# ProPrj_universal-fpga-expansion-board_20.net
KiCad netlist of a schematic drawn in EasyEDA Pro
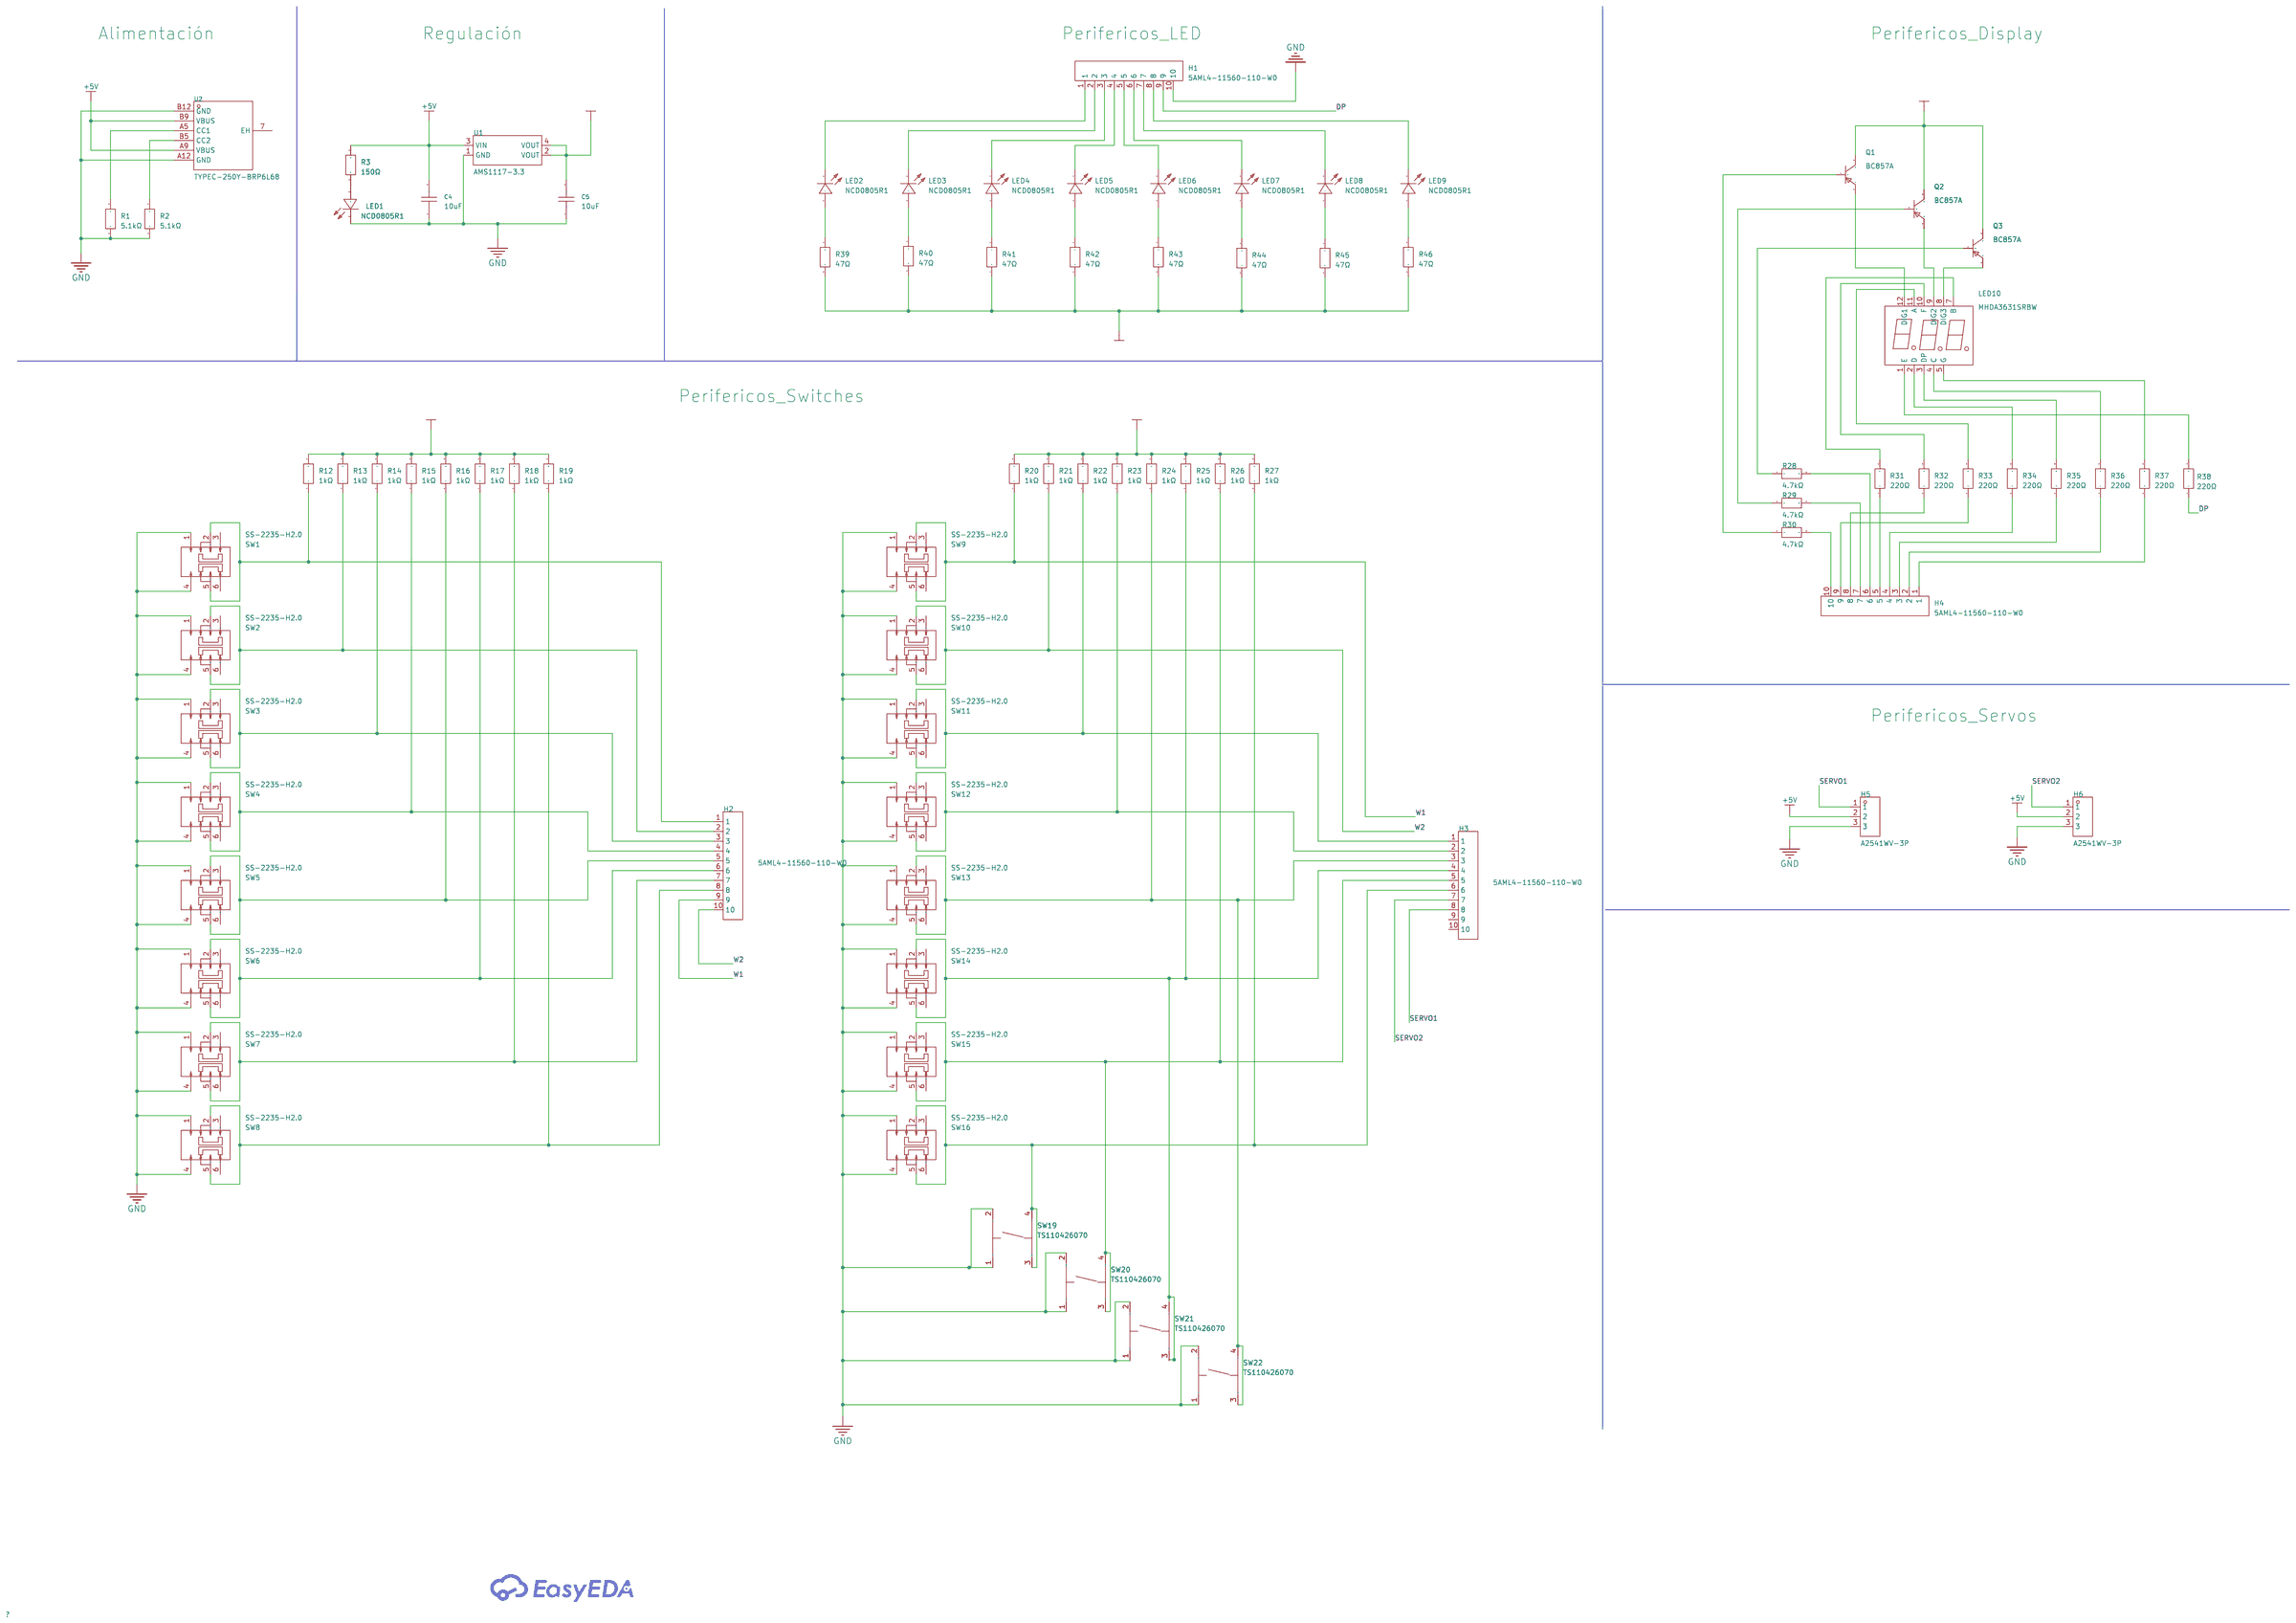
[diagram p0: schematic sheet]

(export (version "E")
  (design (tool "Eeschema 10.0.6"))
  (components
    (comp (ref "C4")
      (value "10uF")
      (footprint "easyedapro:C0603")
      (fields
        (field (name "Manufacturer Part") "CL10A106MQ8NNNC")
        (field (name "Manufacturer") "SAMSUNG(三星)")
      )
      (libsource (lib "easyedapro") (part "CL10A106MQ8NNNC"))
    )
    (comp (ref "C5")
      (value "10uF")
      (footprint "easyedapro:C0603")
      (fields
        (field (name "Manufacturer Part") "CL10A106MQ8NNNC")
        (field (name "Manufacturer") "SAMSUNG(三星)")
      )
      (libsource (lib "easyedapro") (part "CL10A106MQ8NNNC"))
    )
    (comp (ref "H1")
      (value "5AML4-11560-110-W0")
      (footprint "easyedapro:HDR-TH_10P-P2.54-V-M-1")
      (fields (field (name "Manufacturer") "SAMZO(三佐)"))
      (libsource (lib "easyedapro") (part "5AML4-11560-110-W0"))
    )
    (comp (ref "H2")
      (value "5AML4-11560-110-W0")
      (footprint "easyedapro:HDR-TH_10P-P2.54-V-M-1")
      (fields (field (name "Manufacturer") "SAMZO(三佐)"))
      (libsource (lib "easyedapro") (part "5AML4-11560-110-W0"))
    )
    (comp (ref "H3")
      (value "5AML4-11560-110-W0")
      (footprint "easyedapro:HDR-TH_10P-P2.54-V-M-1")
      (fields (field (name "Manufacturer") "SAMZO(三佐)"))
      (libsource (lib "easyedapro") (part "5AML4-11560-110-W0"))
    )
    (comp (ref "H4")
      (value "5AML4-11560-110-W0")
      (footprint "easyedapro:HDR-TH_10P-P2.54-V-M-1")
      (fields (field (name "Manufacturer") "SAMZO(三佐)"))
      (libsource (lib "easyedapro") (part "5AML4-11560-110-W0"))
    )
    (comp (ref "H5")
      (value "A2541WV-3P")
      (footprint "easyedapro:HDR-TH_3P-P2.54-V-M")
      (fields (field (name "Manufacturer") "CJT(长江连接器)"))
      (libsource (lib "easyedapro") (part "A2541WV-3P_C5445396"))
    )
    (comp (ref "H6")
      (value "A2541WV-3P")
      (footprint "easyedapro:HDR-TH_3P-P2.54-V-M")
      (fields (field (name "Manufacturer") "CJT(长江连接器)"))
      (libsource (lib "easyedapro") (part "A2541WV-3P_C5445396"))
    )
    (comp (ref "LED1")
      (value "NCD0805R1")
      (footprint "easyedapro:LED0805-R-RD")
      (fields (field (name "Manufacturer") "国星光电"))
      (libsource (lib "easyedapro") (part "FC-2012HRK-620D"))
    )
    (comp (ref "LED2")
      (value "NCD0805R1")
      (footprint "easyedapro:LED0805-R-RD")
      (fields (field (name "Manufacturer") "国星光电"))
      (libsource (lib "easyedapro") (part "FC-2012HRK-620D"))
    )
    (comp (ref "LED3")
      (value "NCD0805R1")
      (footprint "easyedapro:LED0805-R-RD")
      (fields (field (name "Manufacturer") "国星光电"))
      (libsource (lib "easyedapro") (part "FC-2012HRK-620D"))
    )
    (comp (ref "LED4")
      (value "NCD0805R1")
      (footprint "easyedapro:LED0805-R-RD")
      (fields (field (name "Manufacturer") "国星光电"))
      (libsource (lib "easyedapro") (part "FC-2012HRK-620D"))
    )
    (comp (ref "LED5")
      (value "NCD0805R1")
      (footprint "easyedapro:LED0805-R-RD")
      (fields (field (name "Manufacturer") "国星光电"))
      (libsource (lib "easyedapro") (part "FC-2012HRK-620D"))
    )
    (comp (ref "LED6")
      (value "NCD0805R1")
      (footprint "easyedapro:LED0805-R-RD")
      (fields (field (name "Manufacturer") "国星光电"))
      (libsource (lib "easyedapro") (part "FC-2012HRK-620D"))
    )
    (comp (ref "LED7")
      (value "NCD0805R1")
      (footprint "easyedapro:LED0805-R-RD")
      (fields (field (name "Manufacturer") "国星光电"))
      (libsource (lib "easyedapro") (part "FC-2012HRK-620D"))
    )
    (comp (ref "LED8")
      (value "NCD0805R1")
      (footprint "easyedapro:LED0805-R-RD")
      (fields (field (name "Manufacturer") "国星光电"))
      (libsource (lib "easyedapro") (part "FC-2012HRK-620D"))
    )
    (comp (ref "LED9")
      (value "NCD0805R1")
      (footprint "easyedapro:LED0805-R-RD")
      (fields (field (name "Manufacturer") "国星光电"))
      (libsource (lib "easyedapro") (part "FC-2012HRK-620D"))
    )
    (comp (ref "LED10")
      (value "MHDA3631SRBW")
      (footprint "easyedapro:LED-SEG-TH_11P-L22.5-W14.0-P2.54-S10.18-BL")
      (fields (field (name "Manufacturer") "MEIHUA(美华)"))
      (libsource (lib "easyedapro") (part "MHDA3631SRBW"))
    )
    (comp (ref "Q1")
      (value "BC857A")
      (footprint "easyedapro:SOT-23-3_L3.0-W1.7-P0.95-LS2.9-BR")
      (fields (field (name "Manufacturer") "YFW(佑风微)"))
      (libsource (lib "easyedapro") (part "BC857A_C19626403"))
    )
    (comp (ref "Q2")
      (value "BC857A")
      (footprint "easyedapro:SOT-23-3_L3.0-W1.7-P0.95-LS2.9-BR")
      (fields (field (name "Manufacturer") "YFW(佑风微)"))
      (libsource (lib "easyedapro") (part "BC857A_C19626403"))
    )
    (comp (ref "Q3")
      (value "BC857A")
      (footprint "easyedapro:SOT-23-3_L3.0-W1.7-P0.95-LS2.9-BR")
      (fields (field (name "Manufacturer") "YFW(佑风微)"))
      (libsource (lib "easyedapro") (part "BC857A_C19626403"))
    )
    (comp (ref "R1")
      (value "5.1kΩ")
      (footprint "easyedapro:R1206")
      (fields (field (name "Manufacturer Part") "FRC1206J512 TS") (field (name "Manufacturer") "FOJAN(富捷)"))
      (libsource (lib "easyedapro") (part "FRC1206J512 TS"))
    )
    (comp (ref "R2")
      (value "5.1kΩ")
      (footprint "easyedapro:R1206")
      (fields (field (name "Manufacturer Part") "FRC1206J512 TS") (field (name "Manufacturer") "FOJAN(富捷)"))
      (libsource (lib "easyedapro") (part "FRC1206J512 TS"))
    )
    (comp (ref "R3")
      (value "150Ω")
      (footprint "easyedapro:R1206")
      (fields
        (field (name "Manufacturer Part") "SC1206J1500F8ANRH")
        (field (name "Manufacturer") "Sunway(信维通信)")
      )
      (libsource (lib "easyedapro") (part "SC1206J1500F8ANRH"))
    )
    (comp (ref "R12")
      (value "1kΩ")
      (footprint "easyedapro:R1206")
      (fields (field (name "Manufacturer Part") "AF1206FR-071KL") (field (name "Manufacturer") "YAGEO(国巨)"))
      (libsource (lib "easyedapro") (part "AF1206FR-071KL"))
    )
    (comp (ref "R13")
      (value "1kΩ")
      (footprint "easyedapro:R1206")
      (fields (field (name "Manufacturer Part") "AF1206FR-071KL") (field (name "Manufacturer") "YAGEO(国巨)"))
      (libsource (lib "easyedapro") (part "AF1206FR-071KL"))
    )
    (comp (ref "R14")
      (value "1kΩ")
      (footprint "easyedapro:R1206")
      (fields (field (name "Manufacturer Part") "AF1206FR-071KL") (field (name "Manufacturer") "YAGEO(国巨)"))
      (libsource (lib "easyedapro") (part "AF1206FR-071KL"))
    )
    (comp (ref "R15")
      (value "1kΩ")
      (footprint "easyedapro:R1206")
      (fields (field (name "Manufacturer Part") "AF1206FR-071KL") (field (name "Manufacturer") "YAGEO(国巨)"))
      (libsource (lib "easyedapro") (part "AF1206FR-071KL"))
    )
    (comp (ref "R16")
      (value "1kΩ")
      (footprint "easyedapro:R1206")
      (fields (field (name "Manufacturer Part") "AF1206FR-071KL") (field (name "Manufacturer") "YAGEO(国巨)"))
      (libsource (lib "easyedapro") (part "AF1206FR-071KL"))
    )
    (comp (ref "R17")
      (value "1kΩ")
      (footprint "easyedapro:R1206")
      (fields (field (name "Manufacturer Part") "AF1206FR-071KL") (field (name "Manufacturer") "YAGEO(国巨)"))
      (libsource (lib "easyedapro") (part "AF1206FR-071KL"))
    )
    (comp (ref "R18")
      (value "1kΩ")
      (footprint "easyedapro:R1206")
      (fields (field (name "Manufacturer Part") "AF1206FR-071KL") (field (name "Manufacturer") "YAGEO(国巨)"))
      (libsource (lib "easyedapro") (part "AF1206FR-071KL"))
    )
    (comp (ref "R19")
      (value "1kΩ")
      (footprint "easyedapro:R1206")
      (fields (field (name "Manufacturer Part") "AF1206FR-071KL") (field (name "Manufacturer") "YAGEO(国巨)"))
      (libsource (lib "easyedapro") (part "AF1206FR-071KL"))
    )
    (comp (ref "R20")
      (value "1kΩ")
      (footprint "easyedapro:R1206")
      (fields (field (name "Manufacturer Part") "AF1206FR-071KL") (field (name "Manufacturer") "YAGEO(国巨)"))
      (libsource (lib "easyedapro") (part "AF1206FR-071KL"))
    )
    (comp (ref "R21")
      (value "1kΩ")
      (footprint "easyedapro:R1206")
      (fields (field (name "Manufacturer Part") "AF1206FR-071KL") (field (name "Manufacturer") "YAGEO(国巨)"))
      (libsource (lib "easyedapro") (part "AF1206FR-071KL"))
    )
    (comp (ref "R22")
      (value "1kΩ")
      (footprint "easyedapro:R1206")
      (fields (field (name "Manufacturer Part") "AF1206FR-071KL") (field (name "Manufacturer") "YAGEO(国巨)"))
      (libsource (lib "easyedapro") (part "AF1206FR-071KL"))
    )
    (comp (ref "R23")
      (value "1kΩ")
      (footprint "easyedapro:R1206")
      (fields (field (name "Manufacturer Part") "AF1206FR-071KL") (field (name "Manufacturer") "YAGEO(国巨)"))
      (libsource (lib "easyedapro") (part "AF1206FR-071KL"))
    )
    (comp (ref "R24")
      (value "1kΩ")
      (footprint "easyedapro:R1206")
      (fields (field (name "Manufacturer Part") "AF1206FR-071KL") (field (name "Manufacturer") "YAGEO(国巨)"))
      (libsource (lib "easyedapro") (part "AF1206FR-071KL"))
    )
    (comp (ref "R25")
      (value "1kΩ")
      (footprint "easyedapro:R1206")
      (fields (field (name "Manufacturer Part") "AF1206FR-071KL") (field (name "Manufacturer") "YAGEO(国巨)"))
      (libsource (lib "easyedapro") (part "AF1206FR-071KL"))
    )
    (comp (ref "R26")
      (value "1kΩ")
      (footprint "easyedapro:R1206")
      (fields (field (name "Manufacturer Part") "AF1206FR-071KL") (field (name "Manufacturer") "YAGEO(国巨)"))
      (libsource (lib "easyedapro") (part "AF1206FR-071KL"))
    )
    (comp (ref "R27")
      (value "1kΩ")
      (footprint "easyedapro:R1206")
      (fields (field (name "Manufacturer Part") "AF1206FR-071KL") (field (name "Manufacturer") "YAGEO(国巨)"))
      (libsource (lib "easyedapro") (part "AF1206FR-071KL"))
    )
    (comp (ref "R28")
      (value "4.7kΩ")
      (footprint "easyedapro:R1206")
      (fields (field (name "Manufacturer Part") "FRC1206F4701TS") (field (name "Manufacturer") "FOJAN(富捷)"))
      (libsource (lib "easyedapro") (part "FRC1206F4701TS"))
    )
    (comp (ref "R29")
      (value "4.7kΩ")
      (footprint "easyedapro:R1206")
      (fields (field (name "Manufacturer Part") "FRC1206F4701TS") (field (name "Manufacturer") "FOJAN(富捷)"))
      (libsource (lib "easyedapro") (part "FRC1206F4701TS"))
    )
    (comp (ref "R30")
      (value "4.7kΩ")
      (footprint "easyedapro:R1206")
      (fields (field (name "Manufacturer Part") "FRC1206F4701TS") (field (name "Manufacturer") "FOJAN(富捷)"))
      (libsource (lib "easyedapro") (part "FRC1206F4701TS"))
    )
    (comp (ref "R31")
      (value "220Ω")
      (footprint "easyedapro:R1206")
      (fields (field (name "Manufacturer Part") "RT1206BRD07220RL") (field (name "Manufacturer") "YAGEO(国巨)"))
      (libsource (lib "easyedapro") (part "RT1206BRD07220RL"))
    )
    (comp (ref "R32")
      (value "220Ω")
      (footprint "easyedapro:R1206")
      (fields (field (name "Manufacturer Part") "RT1206BRD07220RL") (field (name "Manufacturer") "YAGEO(国巨)"))
      (libsource (lib "easyedapro") (part "RT1206BRD07220RL"))
    )
    (comp (ref "R33")
      (value "220Ω")
      (footprint "easyedapro:R1206")
      (fields (field (name "Manufacturer Part") "RT1206BRD07220RL") (field (name "Manufacturer") "YAGEO(国巨)"))
      (libsource (lib "easyedapro") (part "RT1206BRD07220RL"))
    )
    (comp (ref "R34")
      (value "220Ω")
      (footprint "easyedapro:R1206")
      (fields (field (name "Manufacturer Part") "RT1206BRD07220RL") (field (name "Manufacturer") "YAGEO(国巨)"))
      (libsource (lib "easyedapro") (part "RT1206BRD07220RL"))
    )
    (comp (ref "R35")
      (value "220Ω")
      (footprint "easyedapro:R1206")
      (fields (field (name "Manufacturer Part") "RT1206BRD07220RL") (field (name "Manufacturer") "YAGEO(国巨)"))
      (libsource (lib "easyedapro") (part "RT1206BRD07220RL"))
    )
    (comp (ref "R36")
      (value "220Ω")
      (footprint "easyedapro:R1206")
      (fields (field (name "Manufacturer Part") "RT1206BRD07220RL") (field (name "Manufacturer") "YAGEO(国巨)"))
      (libsource (lib "easyedapro") (part "RT1206BRD07220RL"))
    )
    (comp (ref "R37")
      (value "220Ω")
      (footprint "easyedapro:R1206")
      (fields (field (name "Manufacturer Part") "RT1206BRD07220RL") (field (name "Manufacturer") "YAGEO(国巨)"))
      (libsource (lib "easyedapro") (part "RT1206BRD07220RL"))
    )
    (comp (ref "R38")
      (value "220Ω")
      (footprint "easyedapro:R1206")
      (fields (field (name "Manufacturer Part") "RT1206BRD07220RL") (field (name "Manufacturer") "YAGEO(国巨)"))
      (libsource (lib "easyedapro") (part "RT1206BRD07220RL"))
    )
    (comp (ref "R39")
      (value "47Ω")
      (footprint "easyedapro:R1206")
      (fields (field (name "Manufacturer Part") "FRC1206J470 TS") (field (name "Manufacturer") "FOJAN(富捷)"))
      (libsource (lib "easyedapro") (part "FRC1206J470 TS"))
    )
    (comp (ref "R40")
      (value "47Ω")
      (footprint "easyedapro:R1206")
      (fields (field (name "Manufacturer Part") "FRC1206J470 TS") (field (name "Manufacturer") "FOJAN(富捷)"))
      (libsource (lib "easyedapro") (part "FRC1206J470 TS"))
    )
    (comp (ref "R41")
      (value "47Ω")
      (footprint "easyedapro:R1206")
      (fields (field (name "Manufacturer Part") "FRC1206J470 TS") (field (name "Manufacturer") "FOJAN(富捷)"))
      (libsource (lib "easyedapro") (part "FRC1206J470 TS"))
    )
    (comp (ref "R42")
      (value "47Ω")
      (footprint "easyedapro:R1206")
      (fields (field (name "Manufacturer Part") "FRC1206J470 TS") (field (name "Manufacturer") "FOJAN(富捷)"))
      (libsource (lib "easyedapro") (part "FRC1206J470 TS"))
    )
    (comp (ref "R43")
      (value "47Ω")
      (footprint "easyedapro:R1206")
      (fields (field (name "Manufacturer Part") "FRC1206J470 TS") (field (name "Manufacturer") "FOJAN(富捷)"))
      (libsource (lib "easyedapro") (part "FRC1206J470 TS"))
    )
    (comp (ref "R44")
      (value "47Ω")
      (footprint "easyedapro:R1206")
      (fields (field (name "Manufacturer Part") "FRC1206J470 TS") (field (name "Manufacturer") "FOJAN(富捷)"))
      (libsource (lib "easyedapro") (part "FRC1206J470 TS"))
    )
    (comp (ref "R45")
      (value "47Ω")
      (footprint "easyedapro:R1206")
      (fields (field (name "Manufacturer Part") "FRC1206J470 TS") (field (name "Manufacturer") "FOJAN(富捷)"))
      (libsource (lib "easyedapro") (part "FRC1206J470 TS"))
    )
    (comp (ref "R46")
      (value "47Ω")
      (footprint "easyedapro:R1206")
      (fields (field (name "Manufacturer Part") "FRC1206J470 TS") (field (name "Manufacturer") "FOJAN(富捷)"))
      (libsource (lib "easyedapro") (part "FRC1206J470 TS"))
    )
    (comp (ref "SW1")
      (value "SS-2235-H2.0")
      (footprint "easyedapro:SW-TH_6P-L9.0-W3.6-P2.50_SS-2235-H2.0")
      (fields (field (name "Manufacturer") "XUNPU(讯普)"))
      (libsource (lib "easyedapro") (part "SS-2235-H2.0"))
    )
    (comp (ref "SW2")
      (value "SS-2235-H2.0")
      (footprint "easyedapro:SW-TH_6P-L9.0-W3.6-P2.50_SS-2235-H2.0")
      (fields (field (name "Manufacturer") "XUNPU(讯普)"))
      (libsource (lib "easyedapro") (part "SS-2235-H2.0"))
    )
    (comp (ref "SW3")
      (value "SS-2235-H2.0")
      (footprint "easyedapro:SW-TH_6P-L9.0-W3.6-P2.50_SS-2235-H2.0")
      (fields (field (name "Manufacturer") "XUNPU(讯普)"))
      (libsource (lib "easyedapro") (part "SS-2235-H2.0"))
    )
    (comp (ref "SW4")
      (value "SS-2235-H2.0")
      (footprint "easyedapro:SW-TH_6P-L9.0-W3.6-P2.50_SS-2235-H2.0")
      (fields (field (name "Manufacturer") "XUNPU(讯普)"))
      (libsource (lib "easyedapro") (part "SS-2235-H2.0"))
    )
    (comp (ref "SW5")
      (value "SS-2235-H2.0")
      (footprint "easyedapro:SW-TH_6P-L9.0-W3.6-P2.50_SS-2235-H2.0")
      (fields (field (name "Manufacturer") "XUNPU(讯普)"))
      (libsource (lib "easyedapro") (part "SS-2235-H2.0"))
    )
    (comp (ref "SW6")
      (value "SS-2235-H2.0")
      (footprint "easyedapro:SW-TH_6P-L9.0-W3.6-P2.50_SS-2235-H2.0")
      (fields (field (name "Manufacturer") "XUNPU(讯普)"))
      (libsource (lib "easyedapro") (part "SS-2235-H2.0"))
    )
    (comp (ref "SW7")
      (value "SS-2235-H2.0")
      (footprint "easyedapro:SW-TH_6P-L9.0-W3.6-P2.50_SS-2235-H2.0")
      (fields (field (name "Manufacturer") "XUNPU(讯普)"))
      (libsource (lib "easyedapro") (part "SS-2235-H2.0"))
    )
    (comp (ref "SW8")
      (value "SS-2235-H2.0")
      (footprint "easyedapro:SW-TH_6P-L9.0-W3.6-P2.50_SS-2235-H2.0")
      (fields (field (name "Manufacturer") "XUNPU(讯普)"))
      (libsource (lib "easyedapro") (part "SS-2235-H2.0"))
    )
    (comp (ref "SW9")
      (value "SS-2235-H2.0")
      (footprint "easyedapro:SW-TH_6P-L9.0-W3.6-P2.50_SS-2235-H2.0")
      (fields (field (name "Manufacturer") "XUNPU(讯普)"))
      (libsource (lib "easyedapro") (part "SS-2235-H2.0"))
    )
    (comp (ref "SW10")
      (value "SS-2235-H2.0")
      (footprint "easyedapro:SW-TH_6P-L9.0-W3.6-P2.50_SS-2235-H2.0")
      (fields (field (name "Manufacturer") "XUNPU(讯普)"))
      (libsource (lib "easyedapro") (part "SS-2235-H2.0"))
    )
    (comp (ref "SW11")
      (value "SS-2235-H2.0")
      (footprint "easyedapro:SW-TH_6P-L9.0-W3.6-P2.50_SS-2235-H2.0")
      (fields (field (name "Manufacturer") "XUNPU(讯普)"))
      (libsource (lib "easyedapro") (part "SS-2235-H2.0"))
    )
    (comp (ref "SW12")
      (value "SS-2235-H2.0")
      (footprint "easyedapro:SW-TH_6P-L9.0-W3.6-P2.50_SS-2235-H2.0")
      (fields (field (name "Manufacturer") "XUNPU(讯普)"))
      (libsource (lib "easyedapro") (part "SS-2235-H2.0"))
    )
    (comp (ref "SW13")
      (value "SS-2235-H2.0")
      (footprint "easyedapro:SW-TH_6P-L9.0-W3.6-P2.50_SS-2235-H2.0")
      (fields (field (name "Manufacturer") "XUNPU(讯普)"))
      (libsource (lib "easyedapro") (part "SS-2235-H2.0"))
    )
    (comp (ref "SW14")
      (value "SS-2235-H2.0")
      (footprint "easyedapro:SW-TH_6P-L9.0-W3.6-P2.50_SS-2235-H2.0")
      (fields (field (name "Manufacturer") "XUNPU(讯普)"))
      (libsource (lib "easyedapro") (part "SS-2235-H2.0"))
    )
    (comp (ref "SW15")
      (value "SS-2235-H2.0")
      (footprint "easyedapro:SW-TH_6P-L9.0-W3.6-P2.50_SS-2235-H2.0")
      (fields (field (name "Manufacturer") "XUNPU(讯普)"))
      (libsource (lib "easyedapro") (part "SS-2235-H2.0"))
    )
    (comp (ref "SW16")
      (value "SS-2235-H2.0")
      (footprint "easyedapro:SW-TH_6P-L9.0-W3.6-P2.50_SS-2235-H2.0")
      (fields (field (name "Manufacturer") "XUNPU(讯普)"))
      (libsource (lib "easyedapro") (part "SS-2235-H2.0"))
    )
    (comp (ref "SW19")
      (value "TS110426070")
      (footprint "easyedapro:SW-SMD_TS110426070")
      (description "Circuit:SPST Actuator Style:Round Button Operating Force:2.6N Switch Height:7mm")
      (fields (field (name "Manufacturer") "HanElectricity(瀚源)"))
      (libsource (lib "easyedapro") (part "TS110426070"))
    )
    (comp (ref "SW20")
      (value "TS110426070")
      (footprint "easyedapro:SW-SMD_TS110426070")
      (description "Circuit:SPST Actuator Style:Round Button Operating Force:2.6N Switch Height:7mm")
      (fields (field (name "Manufacturer") "HanElectricity(瀚源)"))
      (libsource (lib "easyedapro") (part "TS110426070"))
    )
    (comp (ref "SW21")
      (value "TS110426070")
      (footprint "easyedapro:SW-SMD_TS110426070")
      (description "Circuit:SPST Actuator Style:Round Button Operating Force:2.6N Switch Height:7mm")
      (fields (field (name "Manufacturer") "HanElectricity(瀚源)"))
      (libsource (lib "easyedapro") (part "TS110426070"))
    )
    (comp (ref "SW22")
      (value "TS110426070")
      (footprint "easyedapro:SW-SMD_TS110426070")
      (description "Circuit:SPST Actuator Style:Round Button Operating Force:2.6N Switch Height:7mm")
      (fields (field (name "Manufacturer") "HanElectricity(瀚源)"))
      (libsource (lib "easyedapro") (part "TS110426070"))
    )
    (comp (ref "U1")
      (value "AMS1117-3.3")
      (footprint "easyedapro:SOT-223-3_L6.7-W3.7-P2.30-LS7.0-BR")
      (fields (field (name "Manufacturer") "GR(国睿)"))
      (libsource (lib "easyedapro") (part "AMS1117-3.3_C18164485"))
    )
    (comp (ref "U2")
      (value "TYPEC-250Y-BRP6L68")
      (footprint "easyedapro:TYPE-C-SMD_XUNPU_TYPEC-250Y-BRP6L68")
      (description "Connector Type:Type-C Gender:Female")
      (fields (field (name "Manufacturer") "XUNPU(讯普)"))
      (libsource (lib "easyedapro") (part "TYPEC-250Y-BRP6L68"))
    )
  )
  (nets
    (net (code "1") (name "+3.3V") (class "Default")
      (node (ref "C5") (pin "2") (pinfunction "2_2") (pintype "input"))
      (node (ref "Q1") (pin "3") (pinfunction "C_3") (pintype "unspecified"))
      (node (ref "Q2") (pin "3") (pinfunction "C_3") (pintype "unspecified"))
      (node (ref "Q3") (pin "3") (pinfunction "C_3") (pintype "unspecified"))
      (node (ref "R12") (pin "2") (pinfunction "2_2") (pintype "unspecified"))
      (node (ref "R13") (pin "2") (pinfunction "2_2") (pintype "unspecified"))
      (node (ref "R14") (pin "2") (pinfunction "2_2") (pintype "unspecified"))
      (node (ref "R15") (pin "2") (pinfunction "2_2") (pintype "unspecified"))
      (node (ref "R16") (pin "2") (pinfunction "2_2") (pintype "unspecified"))
      (node (ref "R17") (pin "2") (pinfunction "2_2") (pintype "unspecified"))
      (node (ref "R18") (pin "2") (pinfunction "2_2") (pintype "unspecified"))
      (node (ref "R19") (pin "2") (pinfunction "2_2") (pintype "unspecified"))
      (node (ref "R20") (pin "2") (pinfunction "2_2") (pintype "unspecified"))
      (node (ref "R21") (pin "2") (pinfunction "2_2") (pintype "unspecified"))
      (node (ref "R22") (pin "2") (pinfunction "2_2") (pintype "unspecified"))
      (node (ref "R23") (pin "2") (pinfunction "2_2") (pintype "unspecified"))
      (node (ref "R24") (pin "2") (pinfunction "2_2") (pintype "unspecified"))
      (node (ref "R25") (pin "2") (pinfunction "2_2") (pintype "unspecified"))
      (node (ref "R26") (pin "2") (pinfunction "2_2") (pintype "unspecified"))
      (node (ref "R27") (pin "2") (pinfunction "2_2") (pintype "unspecified"))
      (node (ref "R39") (pin "2") (pinfunction "2_2") (pintype "unspecified"))
      (node (ref "R40") (pin "2") (pinfunction "2_2") (pintype "unspecified"))
      (node (ref "R41") (pin "2") (pinfunction "2_2") (pintype "unspecified"))
      (node (ref "R42") (pin "2") (pinfunction "2_2") (pintype "unspecified"))
      (node (ref "R43") (pin "2") (pinfunction "2_2") (pintype "unspecified"))
      (node (ref "R44") (pin "2") (pinfunction "2_2") (pintype "unspecified"))
      (node (ref "R45") (pin "2") (pinfunction "2_2") (pintype "unspecified"))
      (node (ref "R46") (pin "2") (pinfunction "2_2") (pintype "unspecified"))
      (node (ref "U1") (pin "2") (pinfunction "VOUT_2") (pintype "unspecified"))
      (node (ref "U1") (pin "4") (pinfunction "VOUT_4") (pintype "unspecified"))
    )
    (net (code "2") (name "+5V") (class "Default")
      (node (ref "C4") (pin "2") (pinfunction "2_2") (pintype "input"))
      (node (ref "H5") (pin "2") (pinfunction "2_2") (pintype "unspecified"))
      (node (ref "H6") (pin "2") (pinfunction "2_2") (pintype "unspecified"))
      (node (ref "R3") (pin "2") (pinfunction "2_2") (pintype "unspecified"))
      (node (ref "U1") (pin "3") (pinfunction "VIN_3") (pintype "unspecified"))
      (node (ref "U2") (pin "A9") (pinfunction "VBUS_A9") (pintype "input"))
      (node (ref "U2") (pin "B9") (pinfunction "VBUS_B9") (pintype "input"))
    )
    (net (code "3") (name "/DP") (class "Default")
      (node (ref "H1") (pin "9") (pinfunction "9_9") (pintype "unspecified"))
      (node (ref "R38") (pin "1") (pinfunction "1_1") (pintype "unspecified"))
    )
    (net (code "4") (name "/SERVO1") (class "Default")
      (node (ref "H3") (pin "8") (pinfunction "8_8") (pintype "unspecified"))
      (node (ref "H5") (pin "1") (pinfunction "1_1") (pintype "unspecified"))
    )
    (net (code "5") (name "/SERVO2") (class "Default")
      (node (ref "H3") (pin "7") (pinfunction "7_7") (pintype "unspecified"))
      (node (ref "H6") (pin "1") (pinfunction "1_1") (pintype "unspecified"))
    )
    (net (code "6") (name "/W1") (class "Default")
      (node (ref "H2") (pin "9") (pinfunction "9_9") (pintype "unspecified"))
      (node (ref "R20") (pin "1") (pinfunction "1_1") (pintype "unspecified"))
      (node (ref "SW9") (pin "2") (pinfunction "2_2") (pintype "unspecified"))
      (node (ref "SW9") (pin "5") (pinfunction "5_5") (pintype "unspecified"))
    )
    (net (code "7") (name "/W2") (class "Default")
      (node (ref "H2") (pin "10") (pinfunction "10_10") (pintype "unspecified"))
      (node (ref "R21") (pin "1") (pinfunction "1_1") (pintype "unspecified"))
      (node (ref "SW10") (pin "2") (pinfunction "2_2") (pintype "unspecified"))
      (node (ref "SW10") (pin "5") (pinfunction "5_5") (pintype "unspecified"))
    )
    (net (code "8") (name "GND") (class "Default")
      (node (ref "C4") (pin "1") (pinfunction "1_1") (pintype "input"))
      (node (ref "C5") (pin "1") (pinfunction "1_1") (pintype "input"))
      (node (ref "H1") (pin "10") (pinfunction "10_10") (pintype "unspecified"))
      (node (ref "H5") (pin "3") (pinfunction "3_3") (pintype "unspecified"))
      (node (ref "H6") (pin "3") (pinfunction "3_3") (pintype "unspecified"))
      (node (ref "LED1") (pin "2") (pinfunction "-_2") (pintype "unspecified"))
      (node (ref "R1") (pin "1") (pinfunction "1_1") (pintype "unspecified"))
      (node (ref "R2") (pin "1") (pinfunction "1_1") (pintype "unspecified"))
      (node (ref "SW1") (pin "1") (pinfunction "1_1") (pintype "unspecified"))
      (node (ref "SW1") (pin "4") (pinfunction "4_4") (pintype "unspecified"))
      (node (ref "SW10") (pin "1") (pinfunction "1_1") (pintype "unspecified"))
      (node (ref "SW10") (pin "4") (pinfunction "4_4") (pintype "unspecified"))
      (node (ref "SW11") (pin "1") (pinfunction "1_1") (pintype "unspecified"))
      (node (ref "SW11") (pin "4") (pinfunction "4_4") (pintype "unspecified"))
      (node (ref "SW12") (pin "1") (pinfunction "1_1") (pintype "unspecified"))
      (node (ref "SW12") (pin "4") (pinfunction "4_4") (pintype "unspecified"))
      (node (ref "SW13") (pin "1") (pinfunction "1_1") (pintype "unspecified"))
      (node (ref "SW13") (pin "4") (pinfunction "4_4") (pintype "unspecified"))
      (node (ref "SW14") (pin "1") (pinfunction "1_1") (pintype "unspecified"))
      (node (ref "SW14") (pin "4") (pinfunction "4_4") (pintype "unspecified"))
      (node (ref "SW15") (pin "1") (pinfunction "1_1") (pintype "unspecified"))
      (node (ref "SW15") (pin "4") (pinfunction "4_4") (pintype "unspecified"))
      (node (ref "SW16") (pin "1") (pinfunction "1_1") (pintype "unspecified"))
      (node (ref "SW16") (pin "4") (pinfunction "4_4") (pintype "unspecified"))
      (node (ref "SW19") (pin "1") (pinfunction "1_1") (pintype "unspecified"))
      (node (ref "SW19") (pin "2") (pinfunction "2_2") (pintype "unspecified"))
      (node (ref "SW2") (pin "1") (pinfunction "1_1") (pintype "unspecified"))
      (node (ref "SW2") (pin "4") (pinfunction "4_4") (pintype "unspecified"))
      (node (ref "SW20") (pin "1") (pinfunction "1_1") (pintype "unspecified"))
      (node (ref "SW20") (pin "2") (pinfunction "2_2") (pintype "unspecified"))
      (node (ref "SW21") (pin "1") (pinfunction "1_1") (pintype "unspecified"))
      (node (ref "SW21") (pin "2") (pinfunction "2_2") (pintype "unspecified"))
      (node (ref "SW22") (pin "1") (pinfunction "1_1") (pintype "unspecified"))
      (node (ref "SW22") (pin "2") (pinfunction "2_2") (pintype "unspecified"))
      (node (ref "SW3") (pin "1") (pinfunction "1_1") (pintype "unspecified"))
      (node (ref "SW3") (pin "4") (pinfunction "4_4") (pintype "unspecified"))
      (node (ref "SW4") (pin "1") (pinfunction "1_1") (pintype "unspecified"))
      (node (ref "SW4") (pin "4") (pinfunction "4_4") (pintype "unspecified"))
      (node (ref "SW5") (pin "1") (pinfunction "1_1") (pintype "unspecified"))
      (node (ref "SW5") (pin "4") (pinfunction "4_4") (pintype "unspecified"))
      (node (ref "SW6") (pin "1") (pinfunction "1_1") (pintype "unspecified"))
      (node (ref "SW6") (pin "4") (pinfunction "4_4") (pintype "unspecified"))
      (node (ref "SW7") (pin "1") (pinfunction "1_1") (pintype "unspecified"))
      (node (ref "SW7") (pin "4") (pinfunction "4_4") (pintype "unspecified"))
      (node (ref "SW8") (pin "1") (pinfunction "1_1") (pintype "unspecified"))
      (node (ref "SW8") (pin "4") (pinfunction "4_4") (pintype "unspecified"))
      (node (ref "SW9") (pin "1") (pinfunction "1_1") (pintype "unspecified"))
      (node (ref "SW9") (pin "4") (pinfunction "4_4") (pintype "unspecified"))
      (node (ref "U1") (pin "1") (pinfunction "GND_1") (pintype "unspecified"))
      (node (ref "U2") (pin "A12") (pinfunction "GND_A12") (pintype "input"))
      (node (ref "U2") (pin "B12") (pinfunction "GND_B12") (pintype "input"))
    )
    (net (code "9") (name "Net-(H2-Pad1)") (class "Default")
      (node (ref "H2") (pin "1") (pinfunction "1_1") (pintype "unspecified"))
      (node (ref "R12") (pin "1") (pinfunction "1_1") (pintype "unspecified"))
      (node (ref "SW1") (pin "2") (pinfunction "2_2") (pintype "unspecified"))
      (node (ref "SW1") (pin "5") (pinfunction "5_5") (pintype "unspecified"))
    )
    (net (code "10") (name "Net-(H2-Pad2)") (class "Default")
      (node (ref "H2") (pin "2") (pinfunction "2_2") (pintype "unspecified"))
      (node (ref "R13") (pin "1") (pinfunction "1_1") (pintype "unspecified"))
      (node (ref "SW2") (pin "2") (pinfunction "2_2") (pintype "unspecified"))
      (node (ref "SW2") (pin "5") (pinfunction "5_5") (pintype "unspecified"))
    )
    (net (code "11") (name "Net-(H2-Pad3)") (class "Default")
      (node (ref "H2") (pin "3") (pinfunction "3_3") (pintype "unspecified"))
      (node (ref "R14") (pin "1") (pinfunction "1_1") (pintype "unspecified"))
      (node (ref "SW3") (pin "2") (pinfunction "2_2") (pintype "unspecified"))
      (node (ref "SW3") (pin "5") (pinfunction "5_5") (pintype "unspecified"))
    )
    (net (code "12") (name "Net-(H2-Pad4)") (class "Default")
      (node (ref "H2") (pin "4") (pinfunction "4_4") (pintype "unspecified"))
      (node (ref "R15") (pin "1") (pinfunction "1_1") (pintype "unspecified"))
      (node (ref "SW4") (pin "2") (pinfunction "2_2") (pintype "unspecified"))
      (node (ref "SW4") (pin "5") (pinfunction "5_5") (pintype "unspecified"))
    )
    (net (code "13") (name "Net-(H2-Pad5)") (class "Default")
      (node (ref "H2") (pin "5") (pinfunction "5_5") (pintype "unspecified"))
      (node (ref "R16") (pin "1") (pinfunction "1_1") (pintype "unspecified"))
      (node (ref "SW5") (pin "2") (pinfunction "2_2") (pintype "unspecified"))
      (node (ref "SW5") (pin "5") (pinfunction "5_5") (pintype "unspecified"))
    )
    (net (code "14") (name "Net-(H2-Pad6)") (class "Default")
      (node (ref "H2") (pin "6") (pinfunction "6_6") (pintype "unspecified"))
      (node (ref "R17") (pin "1") (pinfunction "1_1") (pintype "unspecified"))
      (node (ref "SW6") (pin "2") (pinfunction "2_2") (pintype "unspecified"))
      (node (ref "SW6") (pin "5") (pinfunction "5_5") (pintype "unspecified"))
    )
    (net (code "15") (name "Net-(H2-Pad7)") (class "Default")
      (node (ref "H2") (pin "7") (pinfunction "7_7") (pintype "unspecified"))
      (node (ref "R18") (pin "1") (pinfunction "1_1") (pintype "unspecified"))
      (node (ref "SW7") (pin "2") (pinfunction "2_2") (pintype "unspecified"))
      (node (ref "SW7") (pin "5") (pinfunction "5_5") (pintype "unspecified"))
    )
    (net (code "16") (name "Net-(H2-Pad8)") (class "Default")
      (node (ref "H2") (pin "8") (pinfunction "8_8") (pintype "unspecified"))
      (node (ref "R19") (pin "1") (pinfunction "1_1") (pintype "unspecified"))
      (node (ref "SW8") (pin "2") (pinfunction "2_2") (pintype "unspecified"))
      (node (ref "SW8") (pin "5") (pinfunction "5_5") (pintype "unspecified"))
    )
    (net (code "17") (name "Net-(H3-Pad1)") (class "Default")
      (node (ref "H3") (pin "1") (pinfunction "1_1") (pintype "unspecified"))
      (node (ref "R22") (pin "1") (pinfunction "1_1") (pintype "unspecified"))
      (node (ref "SW11") (pin "2") (pinfunction "2_2") (pintype "unspecified"))
      (node (ref "SW11") (pin "5") (pinfunction "5_5") (pintype "unspecified"))
    )
    (net (code "18") (name "Net-(H3-Pad2)") (class "Default")
      (node (ref "H3") (pin "2") (pinfunction "2_2") (pintype "unspecified"))
      (node (ref "R23") (pin "1") (pinfunction "1_1") (pintype "unspecified"))
      (node (ref "SW12") (pin "2") (pinfunction "2_2") (pintype "unspecified"))
      (node (ref "SW12") (pin "5") (pinfunction "5_5") (pintype "unspecified"))
    )
    (net (code "19") (name "Net-(H3-Pad3)") (class "Default")
      (node (ref "H3") (pin "3") (pinfunction "3_3") (pintype "unspecified"))
      (node (ref "R24") (pin "1") (pinfunction "1_1") (pintype "unspecified"))
      (node (ref "SW13") (pin "2") (pinfunction "2_2") (pintype "unspecified"))
      (node (ref "SW13") (pin "5") (pinfunction "5_5") (pintype "unspecified"))
      (node (ref "SW22") (pin "3") (pinfunction "3_3") (pintype "unspecified"))
      (node (ref "SW22") (pin "4") (pinfunction "4_4") (pintype "unspecified"))
    )
    (net (code "20") (name "Net-(H3-Pad4)") (class "Default")
      (node (ref "H3") (pin "4") (pinfunction "4_4") (pintype "unspecified"))
      (node (ref "R25") (pin "1") (pinfunction "1_1") (pintype "unspecified"))
      (node (ref "SW14") (pin "2") (pinfunction "2_2") (pintype "unspecified"))
      (node (ref "SW14") (pin "5") (pinfunction "5_5") (pintype "unspecified"))
      (node (ref "SW21") (pin "3") (pinfunction "3_3") (pintype "unspecified"))
      (node (ref "SW21") (pin "4") (pinfunction "4_4") (pintype "unspecified"))
    )
    (net (code "21") (name "Net-(H3-Pad5)") (class "Default")
      (node (ref "H3") (pin "5") (pinfunction "5_5") (pintype "unspecified"))
      (node (ref "R26") (pin "1") (pinfunction "1_1") (pintype "unspecified"))
      (node (ref "SW15") (pin "2") (pinfunction "2_2") (pintype "unspecified"))
      (node (ref "SW15") (pin "5") (pinfunction "5_5") (pintype "unspecified"))
      (node (ref "SW20") (pin "3") (pinfunction "3_3") (pintype "unspecified"))
      (node (ref "SW20") (pin "4") (pinfunction "4_4") (pintype "unspecified"))
    )
    (net (code "22") (name "Net-(H3-Pad6)") (class "Default")
      (node (ref "H3") (pin "6") (pinfunction "6_6") (pintype "unspecified"))
      (node (ref "R27") (pin "1") (pinfunction "1_1") (pintype "unspecified"))
      (node (ref "SW16") (pin "2") (pinfunction "2_2") (pintype "unspecified"))
      (node (ref "SW16") (pin "5") (pinfunction "5_5") (pintype "unspecified"))
      (node (ref "SW19") (pin "3") (pinfunction "3_3") (pintype "unspecified"))
      (node (ref "SW19") (pin "4") (pinfunction "4_4") (pintype "unspecified"))
    )
    (net (code "23") (name "Net-(H4-Pad1)") (class "Default")
      (node (ref "H4") (pin "1") (pinfunction "1_1") (pintype "unspecified"))
      (node (ref "R37") (pin "1") (pinfunction "1_1") (pintype "unspecified"))
    )
    (net (code "24") (name "Net-(H4-Pad2)") (class "Default")
      (node (ref "H4") (pin "2") (pinfunction "2_2") (pintype "unspecified"))
      (node (ref "R36") (pin "1") (pinfunction "1_1") (pintype "unspecified"))
    )
    (net (code "25") (name "Net-(H4-Pad3)") (class "Default")
      (node (ref "H4") (pin "3") (pinfunction "3_3") (pintype "unspecified"))
      (node (ref "R35") (pin "1") (pinfunction "1_1") (pintype "unspecified"))
    )
    (net (code "26") (name "Net-(H4-Pad4)") (class "Default")
      (node (ref "H4") (pin "4") (pinfunction "4_4") (pintype "unspecified"))
      (node (ref "R34") (pin "1") (pinfunction "1_1") (pintype "unspecified"))
    )
    (net (code "27") (name "Net-(H4-Pad5)") (class "Default")
      (node (ref "H4") (pin "5") (pinfunction "5_5") (pintype "unspecified"))
      (node (ref "R31") (pin "1") (pinfunction "1_1") (pintype "unspecified"))
    )
    (net (code "28") (name "Net-(H4-Pad6)") (class "Default")
      (node (ref "H4") (pin "6") (pinfunction "6_6") (pintype "unspecified"))
      (node (ref "R28") (pin "2") (pinfunction "2_2") (pintype "unspecified"))
    )
    (net (code "29") (name "Net-(H4-Pad7)") (class "Default")
      (node (ref "H4") (pin "7") (pinfunction "7_7") (pintype "unspecified"))
      (node (ref "R29") (pin "2") (pinfunction "2_2") (pintype "unspecified"))
    )
    (net (code "30") (name "Net-(H4-Pad8)") (class "Default")
      (node (ref "H4") (pin "8") (pinfunction "8_8") (pintype "unspecified"))
      (node (ref "R32") (pin "1") (pinfunction "1_1") (pintype "unspecified"))
    )
    (net (code "31") (name "Net-(H4-Pad9)") (class "Default")
      (node (ref "H4") (pin "9") (pinfunction "9_9") (pintype "unspecified"))
      (node (ref "R33") (pin "1") (pinfunction "1_1") (pintype "unspecified"))
    )
    (net (code "32") (name "Net-(H4-Pad10)") (class "Default")
      (node (ref "H4") (pin "10") (pinfunction "10_10") (pintype "unspecified"))
      (node (ref "R30") (pin "2") (pinfunction "2_2") (pintype "unspecified"))
    )
    (net (code "33") (name "Net-(LED1-+)") (class "Default")
      (node (ref "LED1") (pin "1") (pinfunction "+_1") (pintype "unspecified"))
      (node (ref "R3") (pin "1") (pinfunction "1_1") (pintype "unspecified"))
    )
    (net (code "34") (name "Net-(LED2-+)") (class "Default")
      (node (ref "LED2") (pin "1") (pinfunction "+_1") (pintype "unspecified"))
      (node (ref "R39") (pin "1") (pinfunction "1_1") (pintype "unspecified"))
    )
    (net (code "35") (name "Net-(LED2--)") (class "Default")
      (node (ref "H1") (pin "1") (pinfunction "1_1") (pintype "unspecified"))
      (node (ref "LED2") (pin "2") (pinfunction "-_2") (pintype "unspecified"))
    )
    (net (code "36") (name "Net-(LED3-+)") (class "Default")
      (node (ref "LED3") (pin "1") (pinfunction "+_1") (pintype "unspecified"))
      (node (ref "R40") (pin "1") (pinfunction "1_1") (pintype "unspecified"))
    )
    (net (code "37") (name "Net-(LED3--)") (class "Default")
      (node (ref "H1") (pin "2") (pinfunction "2_2") (pintype "unspecified"))
      (node (ref "LED3") (pin "2") (pinfunction "-_2") (pintype "unspecified"))
    )
    (net (code "38") (name "Net-(LED4-+)") (class "Default")
      (node (ref "LED4") (pin "1") (pinfunction "+_1") (pintype "unspecified"))
      (node (ref "R41") (pin "1") (pinfunction "1_1") (pintype "unspecified"))
    )
    (net (code "39") (name "Net-(LED4--)") (class "Default")
      (node (ref "H1") (pin "3") (pinfunction "3_3") (pintype "unspecified"))
      (node (ref "LED4") (pin "2") (pinfunction "-_2") (pintype "unspecified"))
    )
    (net (code "40") (name "Net-(LED5-+)") (class "Default")
      (node (ref "LED5") (pin "1") (pinfunction "+_1") (pintype "unspecified"))
      (node (ref "R42") (pin "1") (pinfunction "1_1") (pintype "unspecified"))
    )
    (net (code "41") (name "Net-(LED5--)") (class "Default")
      (node (ref "H1") (pin "4") (pinfunction "4_4") (pintype "unspecified"))
      (node (ref "LED5") (pin "2") (pinfunction "-_2") (pintype "unspecified"))
    )
    (net (code "42") (name "Net-(LED6-+)") (class "Default")
      (node (ref "LED6") (pin "1") (pinfunction "+_1") (pintype "unspecified"))
      (node (ref "R43") (pin "1") (pinfunction "1_1") (pintype "unspecified"))
    )
    (net (code "43") (name "Net-(LED6--)") (class "Default")
      (node (ref "H1") (pin "5") (pinfunction "5_5") (pintype "unspecified"))
      (node (ref "LED6") (pin "2") (pinfunction "-_2") (pintype "unspecified"))
    )
    (net (code "44") (name "Net-(LED7-+)") (class "Default")
      (node (ref "LED7") (pin "1") (pinfunction "+_1") (pintype "unspecified"))
      (node (ref "R44") (pin "1") (pinfunction "1_1") (pintype "unspecified"))
    )
    (net (code "45") (name "Net-(LED7--)") (class "Default")
      (node (ref "H1") (pin "6") (pinfunction "6_6") (pintype "unspecified"))
      (node (ref "LED7") (pin "2") (pinfunction "-_2") (pintype "unspecified"))
    )
    (net (code "46") (name "Net-(LED8-+)") (class "Default")
      (node (ref "LED8") (pin "1") (pinfunction "+_1") (pintype "unspecified"))
      (node (ref "R45") (pin "1") (pinfunction "1_1") (pintype "unspecified"))
    )
    (net (code "47") (name "Net-(LED8--)") (class "Default")
      (node (ref "H1") (pin "7") (pinfunction "7_7") (pintype "unspecified"))
      (node (ref "LED8") (pin "2") (pinfunction "-_2") (pintype "unspecified"))
    )
    (net (code "48") (name "Net-(LED9-+)") (class "Default")
      (node (ref "LED9") (pin "1") (pinfunction "+_1") (pintype "unspecified"))
      (node (ref "R46") (pin "1") (pinfunction "1_1") (pintype "unspecified"))
    )
    (net (code "49") (name "Net-(LED9--)") (class "Default")
      (node (ref "H1") (pin "8") (pinfunction "8_8") (pintype "unspecified"))
      (node (ref "LED9") (pin "2") (pinfunction "-_2") (pintype "unspecified"))
    )
    (net (code "50") (name "Net-(LED10-A)") (class "Default")
      (node (ref "LED10") (pin "11") (pinfunction "A_11") (pintype "unspecified"))
      (node (ref "R33") (pin "2") (pinfunction "2_2") (pintype "unspecified"))
    )
    (net (code "51") (name "Net-(LED10-B)") (class "Default")
      (node (ref "LED10") (pin "7") (pinfunction "B_7") (pintype "unspecified"))
      (node (ref "R31") (pin "2") (pinfunction "2_2") (pintype "unspecified"))
    )
    (net (code "52") (name "Net-(LED10-C)") (class "Default")
      (node (ref "LED10") (pin "4") (pinfunction "C_4") (pintype "unspecified"))
      (node (ref "R36") (pin "2") (pinfunction "2_2") (pintype "unspecified"))
    )
    (net (code "53") (name "Net-(LED10-D)") (class "Default")
      (node (ref "LED10") (pin "2") (pinfunction "D_2") (pintype "unspecified"))
      (node (ref "R34") (pin "2") (pinfunction "2_2") (pintype "unspecified"))
    )
    (net (code "54") (name "Net-(LED10-DIG1)") (class "Default")
      (node (ref "LED10") (pin "12") (pinfunction "DIG1_12") (pintype "unspecified"))
      (node (ref "Q1") (pin "2") (pinfunction "E_2") (pintype "unspecified"))
    )
    (net (code "55") (name "Net-(LED10-DIG2)") (class "Default")
      (node (ref "LED10") (pin "9") (pinfunction "DIG2_9") (pintype "unspecified"))
      (node (ref "Q2") (pin "2") (pinfunction "E_2") (pintype "unspecified"))
    )
    (net (code "56") (name "Net-(LED10-DIG3)") (class "Default")
      (node (ref "LED10") (pin "8") (pinfunction "DIG3_8") (pintype "unspecified"))
      (node (ref "Q3") (pin "2") (pinfunction "E_2") (pintype "unspecified"))
    )
    (net (code "57") (name "Net-(LED10-DP)") (class "Default")
      (node (ref "LED10") (pin "3") (pinfunction "DP_3") (pintype "unspecified"))
      (node (ref "R35") (pin "2") (pinfunction "2_2") (pintype "unspecified"))
    )
    (net (code "58") (name "Net-(LED10-E)") (class "Default")
      (node (ref "LED10") (pin "1") (pinfunction "E_1") (pintype "unspecified"))
      (node (ref "R38") (pin "2") (pinfunction "2_2") (pintype "unspecified"))
    )
    (net (code "59") (name "Net-(LED10-F)") (class "Default")
      (node (ref "LED10") (pin "10") (pinfunction "F_10") (pintype "unspecified"))
      (node (ref "R32") (pin "2") (pinfunction "2_2") (pintype "unspecified"))
    )
    (net (code "60") (name "Net-(LED10-G)") (class "Default")
      (node (ref "LED10") (pin "5") (pinfunction "G_5") (pintype "unspecified"))
      (node (ref "R37") (pin "2") (pinfunction "2_2") (pintype "unspecified"))
    )
    (net (code "61") (name "Net-(Q1-B)") (class "Default")
      (node (ref "Q1") (pin "1") (pinfunction "B_1") (pintype "unspecified"))
      (node (ref "R30") (pin "1") (pinfunction "1_1") (pintype "unspecified"))
    )
    (net (code "62") (name "Net-(Q2-B)") (class "Default")
      (node (ref "Q2") (pin "1") (pinfunction "B_1") (pintype "unspecified"))
      (node (ref "R29") (pin "1") (pinfunction "1_1") (pintype "unspecified"))
    )
    (net (code "63") (name "Net-(Q3-B)") (class "Default")
      (node (ref "Q3") (pin "1") (pinfunction "B_1") (pintype "unspecified"))
      (node (ref "R28") (pin "1") (pinfunction "1_1") (pintype "unspecified"))
    )
    (net (code "64") (name "Net-(U2-CC1)") (class "Default")
      (node (ref "R1") (pin "2") (pinfunction "2_2") (pintype "unspecified"))
      (node (ref "U2") (pin "A5") (pinfunction "CC1_A5") (pintype "input"))
    )
    (net (code "65") (name "Net-(U2-CC2)") (class "Default")
      (node (ref "R2") (pin "2") (pinfunction "2_2") (pintype "unspecified"))
      (node (ref "U2") (pin "B5") (pinfunction "CC2_B5") (pintype "input"))
    )
    (net (code "66") (name "unconnected-(H3-Pad9)") (class "Default")
      (node (ref "H3") (pin "9") (pinfunction "9_9") (pintype "unspecified"))
    )
    (net (code "67") (name "unconnected-(H3-Pad10)") (class "Default")
      (node (ref "H3") (pin "10") (pinfunction "10_10") (pintype "unspecified"))
    )
    (net (code "68") (name "unconnected-(SW1-Pad3)") (class "Default")
      (node (ref "SW1") (pin "3") (pinfunction "3_3") (pintype "unspecified"))
    )
    (net (code "69") (name "unconnected-(SW1-Pad6)") (class "Default")
      (node (ref "SW1") (pin "6") (pinfunction "6_6") (pintype "unspecified"))
    )
    (net (code "70") (name "unconnected-(SW2-Pad3)") (class "Default")
      (node (ref "SW2") (pin "3") (pinfunction "3_3") (pintype "unspecified"))
    )
    (net (code "71") (name "unconnected-(SW2-Pad6)") (class "Default")
      (node (ref "SW2") (pin "6") (pinfunction "6_6") (pintype "unspecified"))
    )
    (net (code "72") (name "unconnected-(SW3-Pad3)") (class "Default")
      (node (ref "SW3") (pin "3") (pinfunction "3_3") (pintype "unspecified"))
    )
    (net (code "73") (name "unconnected-(SW3-Pad6)") (class "Default")
      (node (ref "SW3") (pin "6") (pinfunction "6_6") (pintype "unspecified"))
    )
    (net (code "74") (name "unconnected-(SW4-Pad3)") (class "Default")
      (node (ref "SW4") (pin "3") (pinfunction "3_3") (pintype "unspecified"))
    )
    (net (code "75") (name "unconnected-(SW4-Pad6)") (class "Default")
      (node (ref "SW4") (pin "6") (pinfunction "6_6") (pintype "unspecified"))
    )
    (net (code "76") (name "unconnected-(SW5-Pad3)") (class "Default")
      (node (ref "SW5") (pin "3") (pinfunction "3_3") (pintype "unspecified"))
    )
    (net (code "77") (name "unconnected-(SW5-Pad6)") (class "Default")
      (node (ref "SW5") (pin "6") (pinfunction "6_6") (pintype "unspecified"))
    )
    (net (code "78") (name "unconnected-(SW6-Pad3)") (class "Default")
      (node (ref "SW6") (pin "3") (pinfunction "3_3") (pintype "unspecified"))
    )
    (net (code "79") (name "unconnected-(SW6-Pad6)") (class "Default")
      (node (ref "SW6") (pin "6") (pinfunction "6_6") (pintype "unspecified"))
    )
    (net (code "80") (name "unconnected-(SW7-Pad3)") (class "Default")
      (node (ref "SW7") (pin "3") (pinfunction "3_3") (pintype "unspecified"))
    )
    (net (code "81") (name "unconnected-(SW7-Pad6)") (class "Default")
      (node (ref "SW7") (pin "6") (pinfunction "6_6") (pintype "unspecified"))
    )
    (net (code "82") (name "unconnected-(SW8-Pad3)") (class "Default")
      (node (ref "SW8") (pin "3") (pinfunction "3_3") (pintype "unspecified"))
    )
    (net (code "83") (name "unconnected-(SW8-Pad6)") (class "Default")
      (node (ref "SW8") (pin "6") (pinfunction "6_6") (pintype "unspecified"))
    )
    (net (code "84") (name "unconnected-(SW9-Pad3)") (class "Default")
      (node (ref "SW9") (pin "3") (pinfunction "3_3") (pintype "unspecified"))
    )
    (net (code "85") (name "unconnected-(SW9-Pad6)") (class "Default")
      (node (ref "SW9") (pin "6") (pinfunction "6_6") (pintype "unspecified"))
    )
    (net (code "86") (name "unconnected-(SW10-Pad3)") (class "Default")
      (node (ref "SW10") (pin "3") (pinfunction "3_3") (pintype "unspecified"))
    )
    (net (code "87") (name "unconnected-(SW10-Pad6)") (class "Default")
      (node (ref "SW10") (pin "6") (pinfunction "6_6") (pintype "unspecified"))
    )
    (net (code "88") (name "unconnected-(SW11-Pad3)") (class "Default")
      (node (ref "SW11") (pin "3") (pinfunction "3_3") (pintype "unspecified"))
    )
    (net (code "89") (name "unconnected-(SW11-Pad6)") (class "Default")
      (node (ref "SW11") (pin "6") (pinfunction "6_6") (pintype "unspecified"))
    )
    (net (code "90") (name "unconnected-(SW12-Pad3)") (class "Default")
      (node (ref "SW12") (pin "3") (pinfunction "3_3") (pintype "unspecified"))
    )
    (net (code "91") (name "unconnected-(SW12-Pad6)") (class "Default")
      (node (ref "SW12") (pin "6") (pinfunction "6_6") (pintype "unspecified"))
    )
    (net (code "92") (name "unconnected-(SW13-Pad3)") (class "Default")
      (node (ref "SW13") (pin "3") (pinfunction "3_3") (pintype "unspecified"))
    )
    (net (code "93") (name "unconnected-(SW13-Pad6)") (class "Default")
      (node (ref "SW13") (pin "6") (pinfunction "6_6") (pintype "unspecified"))
    )
    (net (code "94") (name "unconnected-(SW14-Pad3)") (class "Default")
      (node (ref "SW14") (pin "3") (pinfunction "3_3") (pintype "unspecified"))
    )
    (net (code "95") (name "unconnected-(SW14-Pad6)") (class "Default")
      (node (ref "SW14") (pin "6") (pinfunction "6_6") (pintype "unspecified"))
    )
    (net (code "96") (name "unconnected-(SW15-Pad3)") (class "Default")
      (node (ref "SW15") (pin "3") (pinfunction "3_3") (pintype "unspecified"))
    )
    (net (code "97") (name "unconnected-(SW15-Pad6)") (class "Default")
      (node (ref "SW15") (pin "6") (pinfunction "6_6") (pintype "unspecified"))
    )
    (net (code "98") (name "unconnected-(SW16-Pad3)") (class "Default")
      (node (ref "SW16") (pin "3") (pinfunction "3_3") (pintype "unspecified"))
    )
    (net (code "99") (name "unconnected-(SW16-Pad6)") (class "Default")
      (node (ref "SW16") (pin "6") (pinfunction "6_6") (pintype "unspecified"))
    )
    (net (code "100") (name "unconnected-(U2-EH-Pad7)") (class "Default")
      (node (ref "U2") (pin "7") (pinfunction "EH_7") (pintype "input"))
    )
  )
)
